# Limiter.net
KiCad netlist of a schematic drawn in Altium Designer
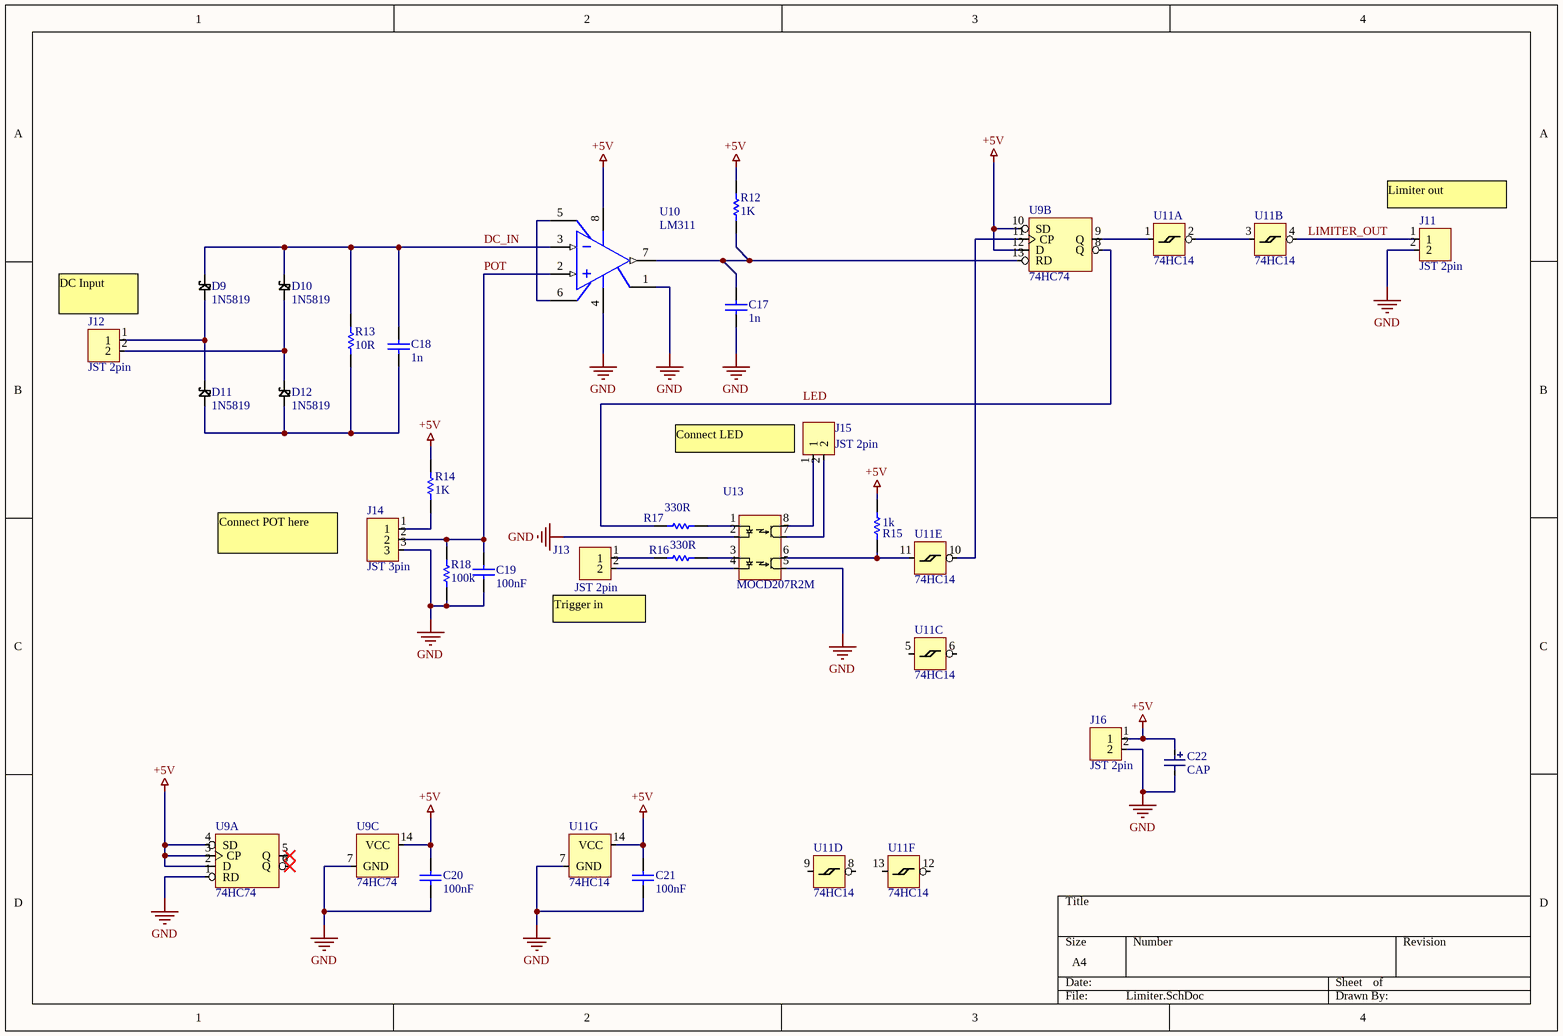
[diagram p0: Limiter.SchDoc]

(export (version "E")
  (design (tool "Eeschema 10.0.6"))
  (components
    (comp (ref "C17")
      (value "1n")
      (footprint "CAPC0805(2012)100_L")
      (description "CAP 100nF 50V ±5% 0805 (2012 Metric) Thickness 1mm SMD")
      (fields (field (name "TOLERANCE") "±5%"))
      (libsource (lib "Altium Content Vault") (part "CMP-1036-04418-1"))
    )
    (comp (ref "C18")
      (value "1n")
      (footprint "CAPC0805(2012)100_L")
      (description "CAP 100nF 50V ±5% 0805 (2012 Metric) Thickness 1mm SMD")
      (fields (field (name "TOLERANCE") "±5%"))
      (libsource (lib "Altium Content Vault") (part "CMP-1036-04418-1"))
    )
    (comp (ref "C19")
      (value "100nF")
      (footprint "CAPC0805(2012)100_L")
      (description "CAP 100nF 50V ±5% 0805 (2012 Metric) Thickness 1mm SMD")
      (fields (field (name "TOLERANCE") "±5%"))
      (libsource (lib "Altium Content Vault") (part "CMP-1036-04418-1"))
    )
    (comp (ref "C20")
      (value "100nF")
      (footprint "CAPC0805(2012)100_L")
      (description "CAP 100nF 50V ±5% 0805 (2012 Metric) Thickness 1mm SMD")
      (fields (field (name "TOLERANCE") "±5%"))
      (libsource (lib "Altium Content Vault") (part "CMP-1036-04418-1"))
    )
    (comp (ref "C21")
      (value "100nF")
      (footprint "CAPC0805(2012)100_L")
      (description "CAP 100nF 50V ±5% 0805 (2012 Metric) Thickness 1mm SMD")
      (fields (field (name "TOLERANCE") "±5%"))
      (libsource (lib "Altium Content Vault") (part "CMP-1036-04418-1"))
    )
    (comp (ref "C22") (value "CAP") (footprint "CAP 2.5mm") (libsource (lib "Schlib1") (part "CAP")))
    (comp (ref "D9") (value "1N5819") (footprint "1N5819") (libsource (lib "Schlib1") (part "1N5819")))
    (comp (ref "D10") (value "1N5819") (footprint "1N5819") (libsource (lib "Schlib1") (part "1N5819")))
    (comp (ref "D11") (value "1N5819") (footprint "1N5819") (libsource (lib "Schlib1") (part "1N5819")))
    (comp (ref "D12") (value "1N5819") (footprint "1N5819") (libsource (lib "Schlib1") (part "1N5819")))
    (comp (ref "J11") (value "JST 2pin") (footprint "JST 2pin") (libsource (lib "") (part "JST 2pin_1")))
    (comp (ref "J12") (value "JST 2pin") (footprint "JST 2pin") (libsource (lib "Schlib1") (part "JST 2pin")))
    (comp (ref "J13") (value "JST 2pin") (footprint "JST 2pin") (libsource (lib "Schlib1") (part "JST 2pin")))
    (comp (ref "J14") (value "JST 3pin") (footprint "JST 3pin") (libsource (lib "Schlib1") (part "JST 3pin")))
    (comp (ref "J15") (value "JST 2pin") (footprint "JST 2pin") (libsource (lib "") (part "JST 2pin_2")))
    (comp (ref "J16") (value "JST 2pin") (footprint "JST 2pin") (libsource (lib "Schlib1") (part "JST 2pin")))
    (comp (ref "R12")
      (value "1K")
      (footprint "RESC0805(2012)_L")
      (description "330R 0.125W 5% 0805 (2012 Metric)  SMD")
      (fields (field (name "TOLERANCE") "5 %") (field (name "POWER") "0.125 W"))
      (libsource (lib "Altium Content Vault") (part "CMP-1013-00062-1"))
    )
    (comp (ref "R13")
      (value "10R")
      (footprint "RESC0805(2012)_L")
      (description "330R 0.125W 5% 0805 (2012 Metric)  SMD")
      (fields (field (name "TOLERANCE") "5 %") (field (name "POWER") "0.125 W"))
      (libsource (lib "Altium Content Vault") (part "CMP-1013-00062-1"))
    )
    (comp (ref "R14")
      (value "1K")
      (footprint "RESC0805(2012)_L")
      (description "330R 0.125W 5% 0805 (2012 Metric)  SMD")
      (fields (field (name "TOLERANCE") "5 %") (field (name "POWER") "0.125 W"))
      (libsource (lib "Altium Content Vault") (part "CMP-1013-00062-1"))
    )
    (comp (ref "R15")
      (value "1k")
      (footprint "RESC0805(2012)_N")
      (description "1K 0.125W 5% 0805 (2012 Metric)  SMD")
      (fields (field (name "POWER") "0.125 W") (field (name "TOLERANCE") "5 %"))
      (libsource (lib "Altium Content Vault") (part "CMP-1013-00074-1"))
    )
    (comp (ref "R16")
      (value "330R")
      (footprint "RESC0805(2012)_L")
      (description "330R 0.125W 5% 0805 (2012 Metric)  SMD")
      (fields (field (name "TOLERANCE") "5 %") (field (name "POWER") "0.125 W"))
      (libsource (lib "Altium Content Vault") (part "CMP-1013-00062-1"))
    )
    (comp (ref "R17")
      (value "330R")
      (footprint "RESC0805(2012)_L")
      (description "330R 0.125W 5% 0805 (2012 Metric)  SMD")
      (fields (field (name "TOLERANCE") "5 %") (field (name "POWER") "0.125 W"))
      (libsource (lib "Altium Content Vault") (part "CMP-1013-00062-1"))
    )
    (comp (ref "R18")
      (value "100k")
      (footprint "RESC0805(2012)_L")
      (description "330R 0.125W 5% 0805 (2012 Metric)  SMD")
      (fields (field (name "TOLERANCE") "5 %") (field (name "POWER") "0.125 W"))
      (libsource (lib "Altium Content Vault") (part "CMP-1013-00062-1"))
    )
    (comp (ref "U9") (value "74HC74") (footprint "SOP14") (libsource (lib "Schlib1") (part "74HC74")))
    (comp (ref "U10") (value "LM311") (footprint "SOIC8-WIDE") (libsource (lib "Schlib1") (part "LM311")))
    (comp (ref "U11") (value "74HC14") (footprint "SOP14") (libsource (lib "Schlib1") (part "74HC14")))
    (comp (ref "U13") (value "MOCD207R2M") (footprint "SOP8") (libsource (lib "Schlib1") (part "MOCD207R2M")))
  )
  (nets
    (net (code "1") (name "+5V") (class "Default")
      (node (ref "C20") (pin "2") (pinfunction "2_2") (pintype "passive"))
      (node (ref "C21") (pin "2") (pinfunction "2_2") (pintype "passive"))
      (node (ref "C22") (pin "2") (pinfunction "2_2") (pintype "passive"))
      (node (ref "J16") (pin "1") (pinfunction "1_1") (pintype "passive"))
      (node (ref "R12") (pin "1") (pinfunction "1_1") (pintype "passive"))
      (node (ref "R14") (pin "1") (pinfunction "1_1") (pintype "passive"))
      (node (ref "R15") (pin "2") (pinfunction "2_2") (pintype "passive"))
      (node (ref "U10") (pin "8") (pinfunction "V+_8") (pintype "power_in"))
      (node (ref "U11") (pin "14") (pinfunction "VCC_14") (pintype "passive"))
      (node (ref "U9") (pin "10") (pinfunction "SD_10") (pintype "passive"))
      (node (ref "U9") (pin "12") (pinfunction "D_12") (pintype "passive"))
      (node (ref "U9") (pin "14") (pinfunction "VCC_14") (pintype "passive"))
      (node (ref "U9") (pin "2") (pinfunction "D_2") (pintype "passive"))
      (node (ref "U9") (pin "3") (pinfunction "CP_3") (pintype "passive"))
      (node (ref "U9") (pin "4") (pinfunction "SD_4") (pintype "passive"))
    )
    (net (code "2") (name "/DC_IN") (class "Default")
      (node (ref "C18") (pin "2") (pinfunction "2_2") (pintype "passive"))
      (node (ref "D10") (pin "K") (pinfunction "K_K") (pintype "passive"))
      (node (ref "D9") (pin "K") (pinfunction "K_K") (pintype "passive"))
      (node (ref "R13") (pin "1") (pinfunction "1_1") (pintype "passive"))
      (node (ref "U10") (pin "3") (pinfunction "IN-_3") (pintype "input"))
    )
    (net (code "3") (name "/LED") (class "Default")
      (node (ref "R17") (pin "2") (pinfunction "2_2") (pintype "passive"))
      (node (ref "U9") (pin "8") (pinfunction "Q_8") (pintype "passive"))
    )
    (net (code "4") (name "/LIMITER_OUT") (class "Default")
      (node (ref "J11") (pin "1") (pinfunction "1_1") (pintype "passive"))
      (node (ref "U11") (pin "4") (pinfunction "4_4") (pintype "passive"))
    )
    (net (code "5") (name "/POT") (class "Default")
      (node (ref "C19") (pin "2") (pinfunction "2_2") (pintype "passive"))
      (node (ref "J14") (pin "2") (pinfunction "2_2") (pintype "passive"))
      (node (ref "R18") (pin "1") (pinfunction "1_1") (pintype "passive"))
      (node (ref "U10") (pin "2") (pinfunction "IN+_2") (pintype "input"))
    )
    (net (code "6") (name "GND") (class "Default")
      (node (ref "C17") (pin "1") (pinfunction "1_1") (pintype "passive"))
      (node (ref "C19") (pin "1") (pinfunction "1_1") (pintype "passive"))
      (node (ref "C20") (pin "1") (pinfunction "1_1") (pintype "passive"))
      (node (ref "C21") (pin "1") (pinfunction "1_1") (pintype "passive"))
      (node (ref "C22") (pin "1") (pinfunction "1_1") (pintype "passive"))
      (node (ref "J11") (pin "2") (pinfunction "2_2") (pintype "passive"))
      (node (ref "J14") (pin "3") (pinfunction "3_3") (pintype "passive"))
      (node (ref "J16") (pin "2") (pinfunction "2_2") (pintype "passive"))
      (node (ref "R18") (pin "2") (pinfunction "2_2") (pintype "passive"))
      (node (ref "U10") (pin "1") (pinfunction "GND_1") (pintype "power_in"))
      (node (ref "U10") (pin "4") (pinfunction "V-_4") (pintype "power_in"))
      (node (ref "U11") (pin "7") (pinfunction "GND_7") (pintype "passive"))
      (node (ref "U13") (pin "2") (pinfunction "2_2") (pintype "passive"))
      (node (ref "U13") (pin "5") (pinfunction "5_5") (pintype "passive"))
      (node (ref "U9") (pin "1") (pinfunction "RD_1") (pintype "passive"))
      (node (ref "U9") (pin "7") (pinfunction "GND_7") (pintype "passive"))
    )
    (net (code "7") (name "Net-(C18-Pad1)") (class "Default")
      (node (ref "C18") (pin "1") (pinfunction "1_1") (pintype "passive"))
      (node (ref "D11") (pin "A") (pinfunction "A_A") (pintype "passive"))
      (node (ref "D12") (pin "A") (pinfunction "A_A") (pintype "passive"))
      (node (ref "R13") (pin "2") (pinfunction "2_2") (pintype "passive"))
    )
    (net (code "8") (name "Net-(D10-PadA)") (class "Default")
      (node (ref "D10") (pin "A") (pinfunction "A_A") (pintype "passive"))
      (node (ref "D12") (pin "K") (pinfunction "K_K") (pintype "passive"))
      (node (ref "J12") (pin "2") (pinfunction "2_2") (pintype "passive"))
    )
    (net (code "9") (name "Net-(D11-PadK)") (class "Default")
      (node (ref "D11") (pin "K") (pinfunction "K_K") (pintype "passive"))
      (node (ref "D9") (pin "A") (pinfunction "A_A") (pintype "passive"))
      (node (ref "J12") (pin "1") (pinfunction "1_1") (pintype "passive"))
    )
    (net (code "10") (name "Net-(J13-Pad1)") (class "Default")
      (node (ref "J13") (pin "1") (pinfunction "1_1") (pintype "passive"))
      (node (ref "R16") (pin "2") (pinfunction "2_2") (pintype "passive"))
    )
    (net (code "11") (name "Net-(J13-Pad2)") (class "Default")
      (node (ref "J13") (pin "2") (pinfunction "2_2") (pintype "passive"))
      (node (ref "U13") (pin "4") (pinfunction "4_4") (pintype "passive"))
    )
    (net (code "12") (name "Net-(J14-Pad1)") (class "Default")
      (node (ref "J14") (pin "1") (pinfunction "1_1") (pintype "passive"))
      (node (ref "R14") (pin "2") (pinfunction "2_2") (pintype "passive"))
    )
    (net (code "13") (name "Net-(J15-Pad1)") (class "Default")
      (node (ref "J15") (pin "1") (pinfunction "1_1") (pintype "passive"))
      (node (ref "U13") (pin "8") (pinfunction "8_8") (pintype "passive"))
    )
    (net (code "14") (name "Net-(J15-Pad2)") (class "Default")
      (node (ref "J15") (pin "2") (pinfunction "2_2") (pintype "passive"))
      (node (ref "U13") (pin "7") (pinfunction "7_7") (pintype "passive"))
    )
    (net (code "15") (name "Net-(R15-Pad1)") (class "Default")
      (node (ref "R15") (pin "1") (pinfunction "1_1") (pintype "passive"))
      (node (ref "U11") (pin "11") (pinfunction "11_11") (pintype "passive"))
      (node (ref "U13") (pin "6") (pinfunction "6_6") (pintype "passive"))
    )
    (net (code "16") (name "Net-(R16-Pad1)") (class "Default")
      (node (ref "R16") (pin "1") (pinfunction "1_1") (pintype "passive"))
      (node (ref "U13") (pin "3") (pinfunction "3_3") (pintype "passive"))
    )
    (net (code "17") (name "Net-(R17-Pad1)") (class "Default")
      (node (ref "R17") (pin "1") (pinfunction "1_1") (pintype "passive"))
      (node (ref "U13") (pin "1") (pinfunction "1_1") (pintype "passive"))
    )
    (net (code "18") (name "Net-(U9B-CP)") (class "Default")
      (node (ref "U11") (pin "10") (pinfunction "10_10") (pintype "passive"))
      (node (ref "U9") (pin "11") (pinfunction "CP_11") (pintype "passive"))
    )
    (net (code "19") (name "Net-(U10-BAL)") (class "Default")
      (node (ref "U10") (pin "5") (pinfunction "BAL_5") (pintype "passive"))
      (node (ref "U10") (pin "6") (pinfunction "BAL/STB_6") (pintype "passive"))
    )
    (net (code "20") (name "Net-(U10-OUT)") (class "Default")
      (node (ref "C17") (pin "2") (pinfunction "2_2") (pintype "passive"))
      (node (ref "R12") (pin "2") (pinfunction "2_2") (pintype "passive"))
      (node (ref "U10") (pin "7") (pinfunction "OUT_7") (pintype "output"))
      (node (ref "U9") (pin "13") (pinfunction "RD_13") (pintype "passive"))
    )
    (net (code "21") (name "Net-(U11-Pad1)") (class "Default")
      (node (ref "U11") (pin "1") (pinfunction "1_1") (pintype "passive"))
      (node (ref "U9") (pin "9") (pinfunction "Q_9") (pintype "passive"))
    )
    (net (code "22") (name "Net-(U11-Pad2)") (class "Default")
      (node (ref "U11") (pin "2") (pinfunction "2_2") (pintype "passive"))
      (node (ref "U11") (pin "3") (pinfunction "3_3") (pintype "passive"))
    )
    (net (code "23") (name "unconnected-(U9A-Q-Pad5)") (class "Default")
      (node (ref "U9") (pin "5") (pinfunction "Q_5") (pintype "passive+no_connect"))
    )
    (net (code "24") (name "unconnected-(U9A-Q-Pad6)") (class "Default")
      (node (ref "U9") (pin "6") (pinfunction "Q_6") (pintype "passive+no_connect"))
    )
    (net (code "25") (name "unconnected-(U11-Pad5)") (class "Default")
      (node (ref "U11") (pin "5") (pinfunction "5_5") (pintype "passive"))
    )
    (net (code "26") (name "unconnected-(U11-Pad6)") (class "Default")
      (node (ref "U11") (pin "6") (pinfunction "6_6") (pintype "passive"))
    )
    (net (code "27") (name "unconnected-(U11-Pad8)") (class "Default")
      (node (ref "U11") (pin "8") (pinfunction "8_8") (pintype "passive"))
    )
    (net (code "28") (name "unconnected-(U11-Pad9)") (class "Default")
      (node (ref "U11") (pin "9") (pinfunction "9_9") (pintype "passive"))
    )
    (net (code "29") (name "unconnected-(U11-Pad12)") (class "Default")
      (node (ref "U11") (pin "12") (pinfunction "12_12") (pintype "passive"))
    )
    (net (code "30") (name "unconnected-(U11-Pad13)") (class "Default")
      (node (ref "U11") (pin "13") (pinfunction "13_13") (pintype "passive"))
    )
  )
)
